# 2_mb_conn.net
KiCad netlist of a schematic drawn in Altium Designer
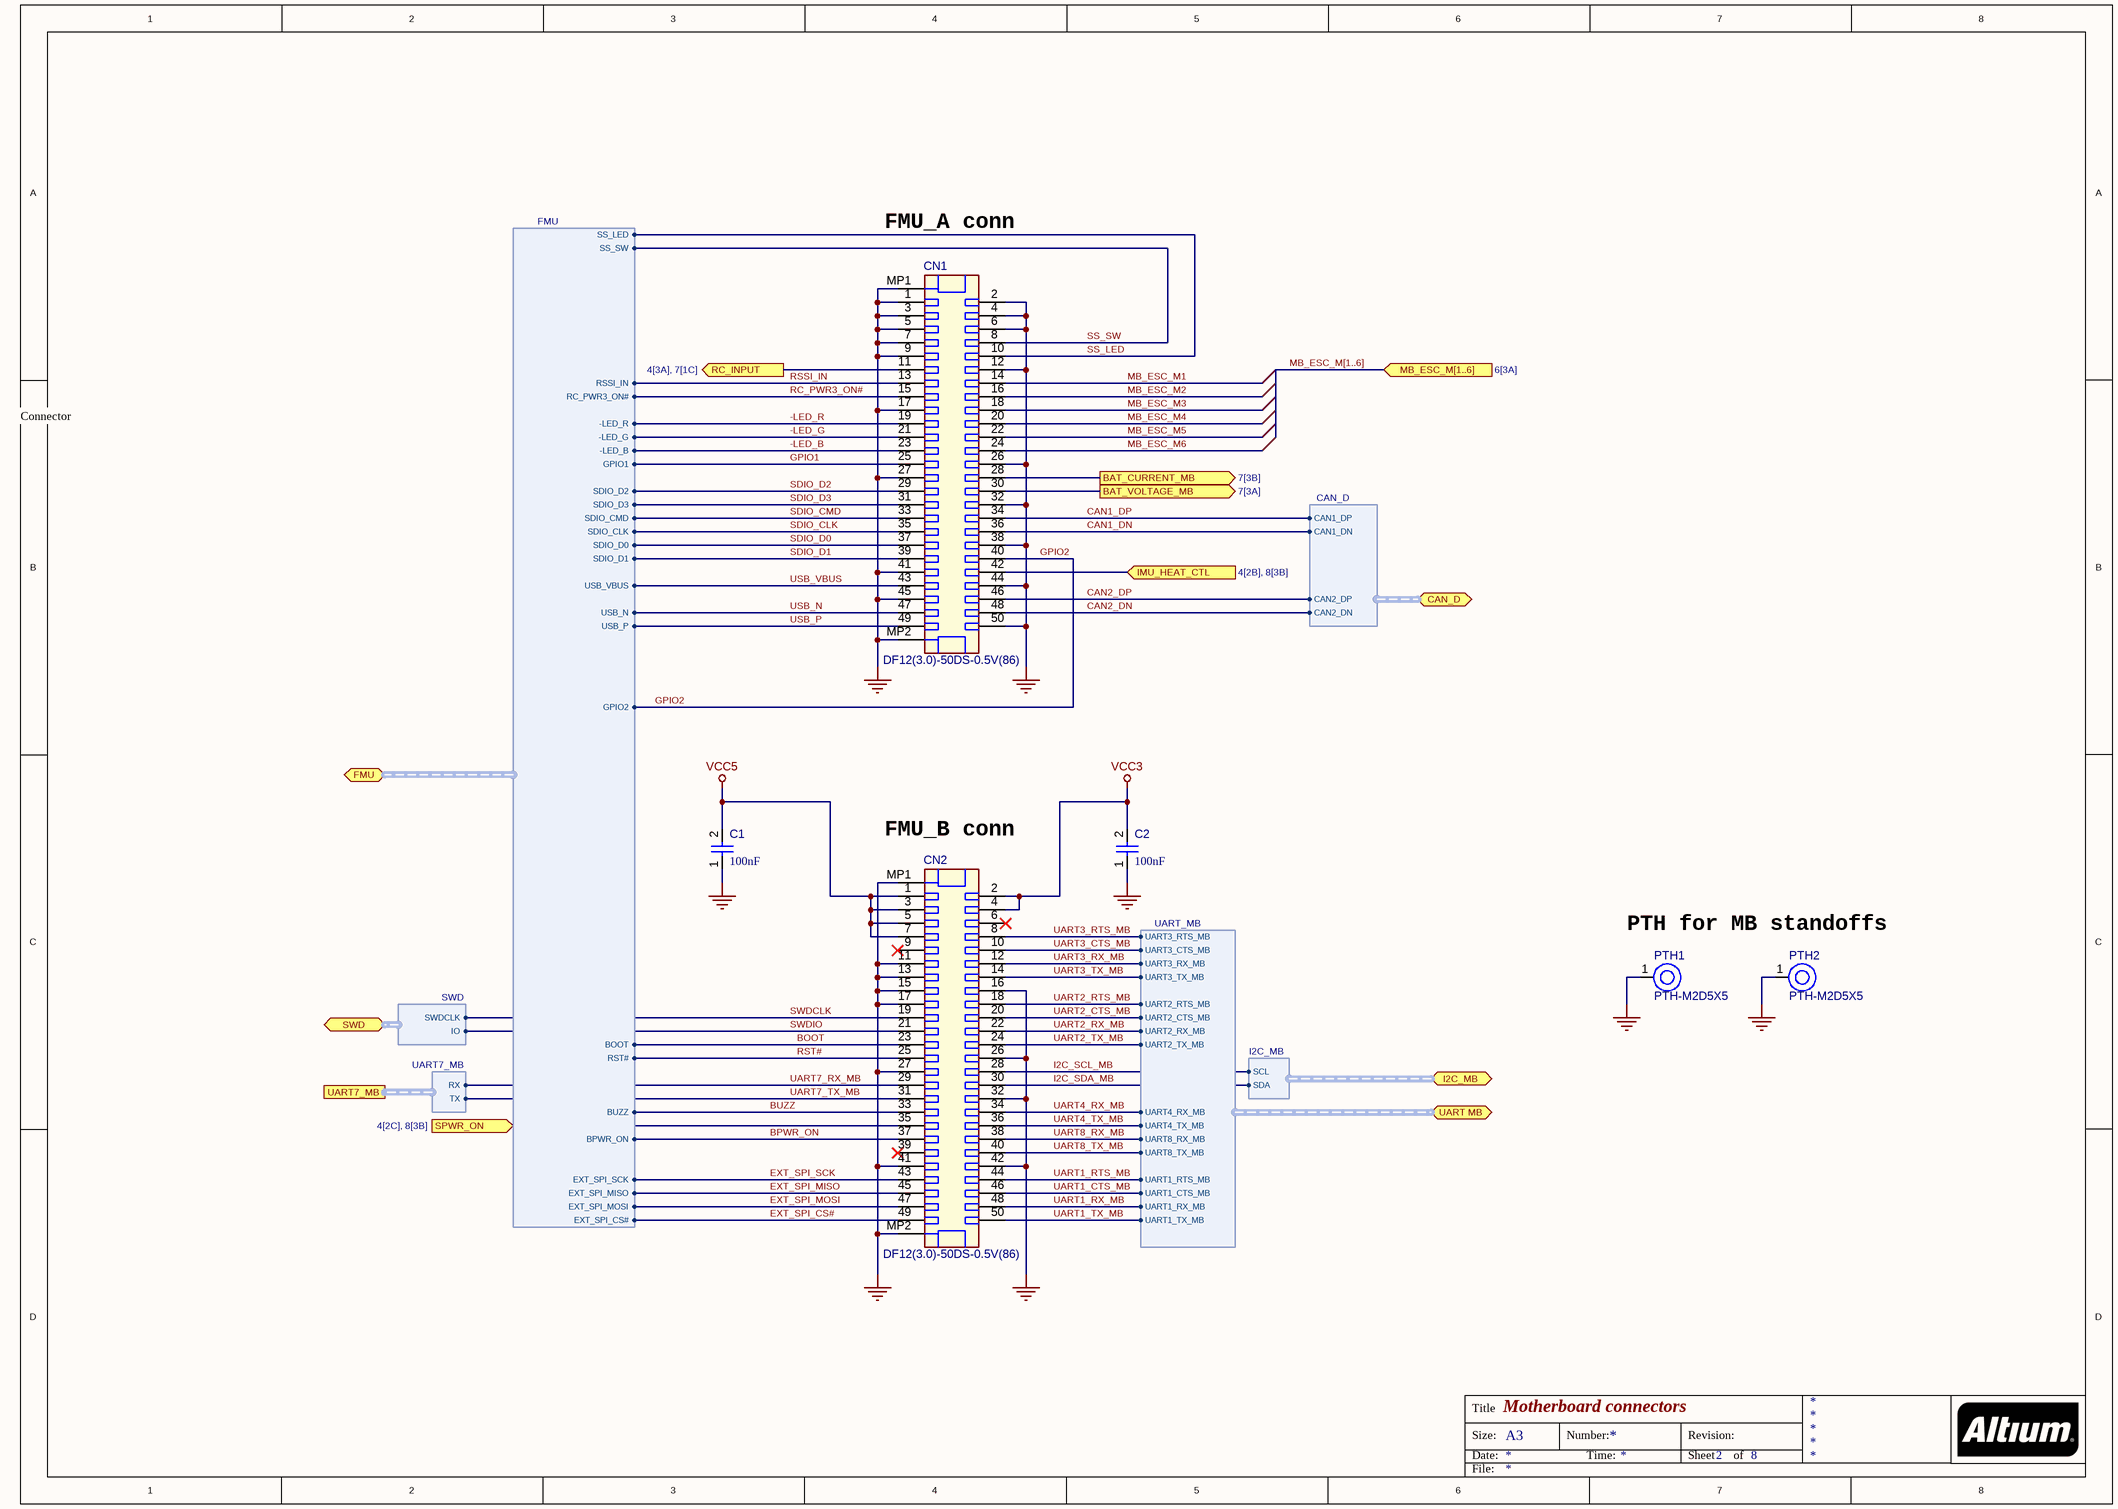
[diagram p0: 2_mb_conn.SchDoc]

(export (version "E")
  (design (tool "Eeschema 10.0.6"))
  (components
    (comp (ref "C1")
      (value "100nF")
      (footprint "CAPC0402(1005)60_L")
      (description "Chip Capacitor, 100nF +/-20%, 10V, 0402, Thickness 0.6 mm")
      (fields (field (name "TOLERANCE") "20%") (field (name "Comment") "Capacitor 100nF +/-20% 10V 0402"))
      (libsource (lib "<Company> Server") (part "CAP-NP-2"))
    )
    (comp (ref "C2")
      (value "100nF")
      (footprint "CAPC0402(1005)60_L")
      (description "Chip Capacitor, 100nF +/-20%, 10V, 0402, Thickness 0.6 mm")
      (fields (field (name "TOLERANCE") "20%") (field (name "Comment") "Capacitor 100nF +/-20% 10V 0402"))
      (libsource (lib "<Company> Server") (part "CAP-NP-2"))
    )
    (comp (ref "CN1")
      (value "DF12(3.0)-50DS-0.5V(86)")
      (footprint "HIRO-DF12(3.0)-50DS-0.5V_V")
      (description "Receptacle Connector, 50 V, 0.3 A, -45 to 125 degC, RoHS, Tape and Reel")
      (libsource (lib "<Company> Server") (part "CMP-00111-4"))
    )
    (comp (ref "CN2")
      (value "DF12(3.0)-50DS-0.5V(86)")
      (footprint "HIRO-DF12(3.0)-50DS-0.5V_V")
      (description "Receptacle Connector, 50 V, 0.3 A, -45 to 125 degC, RoHS, Tape and Reel")
      (libsource (lib "<Company> Server") (part "CMP-00111-4"))
    )
    (comp (ref "PTH1")
      (value "PTH-M2D5X5")
      (footprint "PTH-M2D5X5")
      (description "M2 PTH (2.5mm), 5mm pad")
      (libsource (lib "<Company> Server") (part "CMP-00028-00000-1"))
    )
    (comp (ref "PTH2")
      (value "PTH-M2D5X5")
      (footprint "PTH-M2D5X5")
      (description "M2 PTH (2.5mm), 5mm pad")
      (libsource (lib "<Company> Server") (part "CMP-00028-00000-1"))
    )
  )
  (nets
    (net (code "7") (name "/-LED_B") (class "Default")
      (node (ref "CN1") (pin "23") (pinfunction "23_23") (pintype "passive"))
    )
    (net (code "8") (name "/-LED_G") (class "Default")
      (node (ref "CN1") (pin "21") (pinfunction "21_21") (pintype "passive"))
    )
    (net (code "9") (name "/-LED_R") (class "Default")
      (node (ref "CN1") (pin "19") (pinfunction "19_19") (pintype "passive"))
    )
    (net (code "10") (name "/BAT_CURRENT_MB") (class "Default")
      (node (ref "CN1") (pin "28") (pinfunction "28_28") (pintype "passive"))
    )
    (net (code "11") (name "/BAT_VOLTAGE_MB") (class "Default")
      (node (ref "CN1") (pin "30") (pinfunction "30_30") (pintype "passive"))
    )
    (net (code "12") (name "/BOOT") (class "Default")
      (node (ref "CN2") (pin "23") (pinfunction "23_23") (pintype "passive"))
    )
    (net (code "13") (name "/BPWR_ON") (class "Default")
      (node (ref "CN2") (pin "37") (pinfunction "37_37") (pintype "passive"))
    )
    (net (code "14") (name "/BUZZ") (class "Default")
      (node (ref "CN2") (pin "33") (pinfunction "33_33") (pintype "passive"))
    )
    (net (code "15") (name "/CAN1_DN") (class "Default")
      (node (ref "CN1") (pin "36") (pinfunction "36_36") (pintype "passive"))
    )
    (net (code "16") (name "/CAN1_DP") (class "Default")
      (node (ref "CN1") (pin "34") (pinfunction "34_34") (pintype "passive"))
    )
    (net (code "17") (name "/CAN2_DN") (class "Default")
      (node (ref "CN1") (pin "48") (pinfunction "48_48") (pintype "passive"))
    )
    (net (code "18") (name "/CAN2_DP") (class "Default")
      (node (ref "CN1") (pin "46") (pinfunction "46_46") (pintype "passive"))
    )
    (net (code "19") (name "/EXT_SPI_CS#") (class "Default")
      (node (ref "CN2") (pin "49") (pinfunction "49_49") (pintype "passive"))
    )
    (net (code "20") (name "/EXT_SPI_MISO") (class "Default")
      (node (ref "CN2") (pin "45") (pinfunction "45_45") (pintype "passive"))
    )
    (net (code "21") (name "/EXT_SPI_MOSI") (class "Default")
      (node (ref "CN2") (pin "47") (pinfunction "47_47") (pintype "passive"))
    )
    (net (code "22") (name "/EXT_SPI_SCK") (class "Default")
      (node (ref "CN2") (pin "43") (pinfunction "43_43") (pintype "passive"))
    )
    (net (code "23") (name "/GPIO1") (class "Default")
      (node (ref "CN1") (pin "25") (pinfunction "25_25") (pintype "passive"))
    )
    (net (code "24") (name "/GPIO2") (class "Default")
      (node (ref "CN1") (pin "40") (pinfunction "40_40") (pintype "passive"))
    )
    (net (code "25") (name "/I2C_SCL_MB") (class "Default")
      (node (ref "CN2") (pin "28") (pinfunction "28_28") (pintype "passive"))
    )
    (net (code "26") (name "/I2C_SDA_MB") (class "Default")
      (node (ref "CN2") (pin "30") (pinfunction "30_30") (pintype "passive"))
    )
    (net (code "27") (name "/IMU_HEAT_CTL") (class "Default")
      (node (ref "CN1") (pin "42") (pinfunction "42_42") (pintype "passive"))
    )
    (net (code "28") (name "/MB_ESC_M1") (class "Default")
      (node (ref "CN1") (pin "14") (pinfunction "14_14") (pintype "passive"))
    )
    (net (code "29") (name "/MB_ESC_M2") (class "Default")
      (node (ref "CN1") (pin "16") (pinfunction "16_16") (pintype "passive"))
    )
    (net (code "30") (name "/MB_ESC_M3") (class "Default")
      (node (ref "CN1") (pin "18") (pinfunction "18_18") (pintype "passive"))
    )
    (net (code "31") (name "/MB_ESC_M4") (class "Default")
      (node (ref "CN1") (pin "20") (pinfunction "20_20") (pintype "passive"))
    )
    (net (code "32") (name "/MB_ESC_M5") (class "Default")
      (node (ref "CN1") (pin "22") (pinfunction "22_22") (pintype "passive"))
    )
    (net (code "33") (name "/MB_ESC_M6") (class "Default")
      (node (ref "CN1") (pin "24") (pinfunction "24_24") (pintype "passive"))
    )
    (net (code "35") (name "/RC_INPUT") (class "Default")
      (node (ref "CN1") (pin "11") (pinfunction "11_11") (pintype "passive"))
    )
    (net (code "36") (name "/RC_PWR3_ON#") (class "Default")
      (node (ref "CN1") (pin "15") (pinfunction "15_15") (pintype "passive"))
    )
    (net (code "37") (name "/RSSI_IN") (class "Default")
      (node (ref "CN1") (pin "13") (pinfunction "13_13") (pintype "passive"))
    )
    (net (code "38") (name "/RST#") (class "Default")
      (node (ref "CN2") (pin "25") (pinfunction "25_25") (pintype "passive"))
    )
    (net (code "39") (name "/SDIO_CLK") (class "Default")
      (node (ref "CN1") (pin "35") (pinfunction "35_35") (pintype "passive"))
    )
    (net (code "40") (name "/SDIO_CMD") (class "Default")
      (node (ref "CN1") (pin "33") (pinfunction "33_33") (pintype "passive"))
    )
    (net (code "41") (name "/SDIO_D0") (class "Default")
      (node (ref "CN1") (pin "37") (pinfunction "37_37") (pintype "passive"))
    )
    (net (code "42") (name "/SDIO_D1") (class "Default")
      (node (ref "CN1") (pin "39") (pinfunction "39_39") (pintype "passive"))
    )
    (net (code "43") (name "/SDIO_D2") (class "Default")
      (node (ref "CN1") (pin "29") (pinfunction "29_29") (pintype "passive"))
    )
    (net (code "44") (name "/SDIO_D3") (class "Default")
      (node (ref "CN1") (pin "31") (pinfunction "31_31") (pintype "passive"))
    )
    (net (code "45") (name "/SPWR_ON") (class "Default")
      (node (ref "CN2") (pin "35") (pinfunction "35_35") (pintype "passive"))
    )
    (net (code "46") (name "/SS_LED") (class "Default")
      (node (ref "CN1") (pin "10") (pinfunction "10_10") (pintype "passive"))
    )
    (net (code "47") (name "/SS_SW") (class "Default")
      (node (ref "CN1") (pin "8") (pinfunction "8_8") (pintype "passive"))
    )
    (net (code "48") (name "/SWDCLK") (class "Default")
      (node (ref "CN2") (pin "19") (pinfunction "19_19") (pintype "passive"))
    )
    (net (code "49") (name "/SWDIO") (class "Default")
      (node (ref "CN2") (pin "21") (pinfunction "21_21") (pintype "passive"))
    )
    (net (code "50") (name "/UART1_CTS_MB") (class "Default")
      (node (ref "CN2") (pin "46") (pinfunction "46_46") (pintype "passive"))
    )
    (net (code "51") (name "/UART1_RTS_MB") (class "Default")
      (node (ref "CN2") (pin "44") (pinfunction "44_44") (pintype "passive"))
    )
    (net (code "52") (name "/UART1_RX_MB") (class "Default")
      (node (ref "CN2") (pin "48") (pinfunction "48_48") (pintype "passive"))
    )
    (net (code "53") (name "/UART1_TX_MB") (class "Default")
      (node (ref "CN2") (pin "50") (pinfunction "50_50") (pintype "passive"))
    )
    (net (code "54") (name "/UART2_CTS_MB") (class "Default")
      (node (ref "CN2") (pin "20") (pinfunction "20_20") (pintype "passive"))
    )
    (net (code "55") (name "/UART2_RTS_MB") (class "Default")
      (node (ref "CN2") (pin "18") (pinfunction "18_18") (pintype "passive"))
    )
    (net (code "56") (name "/UART2_RX_MB") (class "Default")
      (node (ref "CN2") (pin "22") (pinfunction "22_22") (pintype "passive"))
    )
    (net (code "57") (name "/UART2_TX_MB") (class "Default")
      (node (ref "CN2") (pin "24") (pinfunction "24_24") (pintype "passive"))
    )
    (net (code "58") (name "/UART3_CTS_MB") (class "Default")
      (node (ref "CN2") (pin "10") (pinfunction "10_10") (pintype "passive"))
    )
    (net (code "59") (name "/UART3_RTS_MB") (class "Default")
      (node (ref "CN2") (pin "8") (pinfunction "8_8") (pintype "passive"))
    )
    (net (code "60") (name "/UART3_RX_MB") (class "Default")
      (node (ref "CN2") (pin "12") (pinfunction "12_12") (pintype "passive"))
    )
    (net (code "61") (name "/UART3_TX_MB") (class "Default")
      (node (ref "CN2") (pin "14") (pinfunction "14_14") (pintype "passive"))
    )
    (net (code "62") (name "/UART4_RX_MB") (class "Default")
      (node (ref "CN2") (pin "34") (pinfunction "34_34") (pintype "passive"))
    )
    (net (code "63") (name "/UART4_TX_MB") (class "Default")
      (node (ref "CN2") (pin "36") (pinfunction "36_36") (pintype "passive"))
    )
    (net (code "64") (name "/UART7_RX_MB") (class "Default")
      (node (ref "CN2") (pin "29") (pinfunction "29_29") (pintype "passive"))
    )
    (net (code "65") (name "/UART7_TX_MB") (class "Default")
      (node (ref "CN2") (pin "31") (pinfunction "31_31") (pintype "passive"))
    )
    (net (code "66") (name "/UART8_RX_MB") (class "Default")
      (node (ref "CN2") (pin "38") (pinfunction "38_38") (pintype "passive"))
    )
    (net (code "67") (name "/UART8_TX_MB") (class "Default")
      (node (ref "CN2") (pin "40") (pinfunction "40_40") (pintype "passive"))
    )
    (net (code "68") (name "/USB_N") (class "Default")
      (node (ref "CN1") (pin "47") (pinfunction "47_47") (pintype "passive"))
    )
    (net (code "69") (name "/USB_P") (class "Default")
      (node (ref "CN1") (pin "49") (pinfunction "49_49") (pintype "passive"))
    )
    (net (code "70") (name "/USB_VBUS") (class "Default")
      (node (ref "CN1") (pin "43") (pinfunction "43_43") (pintype "passive"))
    )
    (net (code "77") (name "GND") (class "Default")
      (node (ref "C1") (pin "1") (pinfunction "1_1") (pintype "passive"))
      (node (ref "C2") (pin "1") (pinfunction "1_1") (pintype "passive"))
      (node (ref "CN1") (pin "1") (pinfunction "1_1") (pintype "passive"))
      (node (ref "CN1") (pin "12") (pinfunction "12_12") (pintype "passive"))
      (node (ref "CN1") (pin "17") (pinfunction "17_17") (pintype "passive"))
      (node (ref "CN1") (pin "2") (pinfunction "2_2") (pintype "passive"))
      (node (ref "CN1") (pin "26") (pinfunction "26_26") (pintype "passive"))
      (node (ref "CN1") (pin "27") (pinfunction "27_27") (pintype "passive"))
      (node (ref "CN1") (pin "3") (pinfunction "3_3") (pintype "passive"))
      (node (ref "CN1") (pin "32") (pinfunction "32_32") (pintype "passive"))
      (node (ref "CN1") (pin "38") (pinfunction "38_38") (pintype "passive"))
      (node (ref "CN1") (pin "4") (pinfunction "4_4") (pintype "passive"))
      (node (ref "CN1") (pin "41") (pinfunction "41_41") (pintype "passive"))
      (node (ref "CN1") (pin "44") (pinfunction "44_44") (pintype "passive"))
      (node (ref "CN1") (pin "45") (pinfunction "45_45") (pintype "passive"))
      (node (ref "CN1") (pin "5") (pinfunction "5_5") (pintype "passive"))
      (node (ref "CN1") (pin "50") (pinfunction "50_50") (pintype "passive"))
      (node (ref "CN1") (pin "6") (pinfunction "6_6") (pintype "passive"))
      (node (ref "CN1") (pin "7") (pinfunction "7_7") (pintype "passive"))
      (node (ref "CN1") (pin "9") (pinfunction "9_9") (pintype "passive"))
      (node (ref "CN1") (pin "MP1") (pinfunction "MP1_MP1") (pintype "passive"))
      (node (ref "CN1") (pin "MP2") (pinfunction "MP2_MP2") (pintype "passive"))
      (node (ref "CN2") (pin "11") (pinfunction "11_11") (pintype "passive"))
      (node (ref "CN2") (pin "13") (pinfunction "13_13") (pintype "passive"))
      (node (ref "CN2") (pin "15") (pinfunction "15_15") (pintype "passive"))
      (node (ref "CN2") (pin "16") (pinfunction "16_16") (pintype "passive"))
      (node (ref "CN2") (pin "17") (pinfunction "17_17") (pintype "passive"))
      (node (ref "CN2") (pin "26") (pinfunction "26_26") (pintype "passive"))
      (node (ref "CN2") (pin "27") (pinfunction "27_27") (pintype "passive"))
      (node (ref "CN2") (pin "32") (pinfunction "32_32") (pintype "passive"))
      (node (ref "CN2") (pin "41") (pinfunction "41_41") (pintype "passive"))
      (node (ref "CN2") (pin "42") (pinfunction "42_42") (pintype "passive"))
      (node (ref "CN2") (pin "MP1") (pinfunction "MP1_MP1") (pintype "passive"))
      (node (ref "CN2") (pin "MP2") (pinfunction "MP2_MP2") (pintype "passive"))
      (node (ref "PTH1") (pin "1") (pinfunction "H1_1") (pintype "passive"))
      (node (ref "PTH2") (pin "1") (pinfunction "H1_1") (pintype "passive"))
    )
    (net (code "78") (name "VCC3") (class "Default")
      (node (ref "C2") (pin "2") (pinfunction "2_2") (pintype "passive"))
      (node (ref "CN2") (pin "2") (pinfunction "2_2") (pintype "passive"))
      (node (ref "CN2") (pin "4") (pinfunction "4_4") (pintype "passive"))
    )
    (net (code "79") (name "VCC5") (class "Default")
      (node (ref "C1") (pin "2") (pinfunction "2_2") (pintype "passive"))
      (node (ref "CN2") (pin "1") (pinfunction "1_1") (pintype "passive"))
      (node (ref "CN2") (pin "3") (pinfunction "3_3") (pintype "passive"))
      (node (ref "CN2") (pin "5") (pinfunction "5_5") (pintype "passive"))
      (node (ref "CN2") (pin "7") (pinfunction "7_7") (pintype "passive"))
    )
    (net (code "80") (name "unconnected-(CN2-Pad6)") (class "Default")
      (node (ref "CN2") (pin "6") (pinfunction "6_6") (pintype "passive+no_connect"))
    )
    (net (code "81") (name "unconnected-(CN2-Pad9)") (class "Default")
      (node (ref "CN2") (pin "9") (pinfunction "9_9") (pintype "passive+no_connect"))
    )
    (net (code "82") (name "unconnected-(CN2-Pad39)") (class "Default")
      (node (ref "CN2") (pin "39") (pinfunction "39_39") (pintype "passive+no_connect"))
    )
  )
)
